# LightSensorCircuitNoAmp_BTSeriesHookup.net
KiCad netlist of a schematic drawn in EAGLE
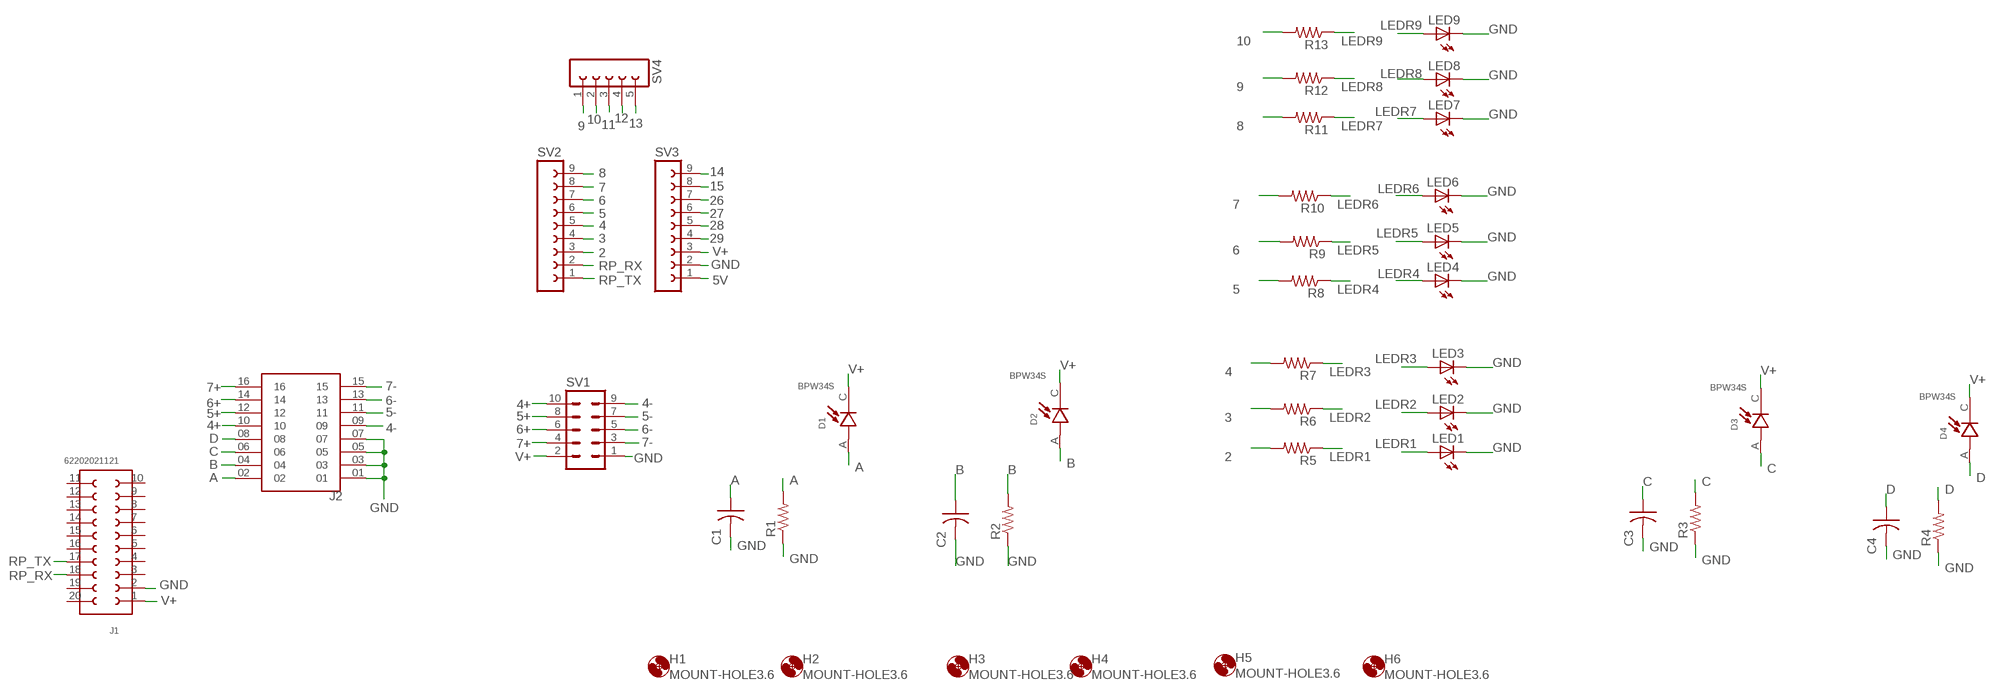
[diagram p0: schematic, sheet 1]

(export (version "E")
  (design (tool "Eeschema 10.0.6"))
  (components
    (comp (ref "C1")
      (value "C-US025-025X050")
      (footprint "eagle-import:C025-025X050")
      (libsource (lib "eagle-import") (part "C-US025-025X050"))
    )
    (comp (ref "C2")
      (value "C-US025-025X050")
      (footprint "eagle-import:C025-025X050")
      (libsource (lib "eagle-import") (part "C-US025-025X050"))
    )
    (comp (ref "C3")
      (value "C-US025-025X050")
      (footprint "eagle-import:C025-025X050")
      (libsource (lib "eagle-import") (part "C-US025-025X050"))
    )
    (comp (ref "C4")
      (value "C-US025-025X050")
      (footprint "eagle-import:C025-025X050")
      (libsource (lib "eagle-import") (part "C-US025-025X050"))
    )
    (comp (ref "D1")
      (value "BPW34S")
      (footprint "eagle-import:DIO_BPW34S")
      (fields (field (name "MF") "Vishay Semiconductor Opto Division"))
      (libsource (lib "eagle-import") (part "BPW34S"))
    )
    (comp (ref "D2")
      (value "BPW34S")
      (footprint "eagle-import:DIO_BPW34S")
      (fields (field (name "MF") "Vishay Semiconductor Opto Division"))
      (libsource (lib "eagle-import") (part "BPW34S"))
    )
    (comp (ref "D3")
      (value "BPW34S")
      (footprint "eagle-import:DIO_BPW34S")
      (fields (field (name "MF") "Vishay Semiconductor Opto Division"))
      (libsource (lib "eagle-import") (part "BPW34S"))
    )
    (comp (ref "D4")
      (value "BPW34S")
      (footprint "eagle-import:DIO_BPW34S")
      (fields (field (name "MF") "Vishay Semiconductor Opto Division"))
      (libsource (lib "eagle-import") (part "BPW34S"))
    )
    (comp (ref "H1")
      (value "MOUNT-HOLE3.6")
      (footprint "eagle-import:3,6")
      (libsource (lib "eagle-import") (part "MOUNT-HOLE3.6"))
    )
    (comp (ref "H2")
      (value "MOUNT-HOLE3.6")
      (footprint "eagle-import:3,6")
      (libsource (lib "eagle-import") (part "MOUNT-HOLE3.6"))
    )
    (comp (ref "H3")
      (value "MOUNT-HOLE3.6")
      (footprint "eagle-import:3,6")
      (libsource (lib "eagle-import") (part "MOUNT-HOLE3.6"))
    )
    (comp (ref "H4")
      (value "MOUNT-HOLE3.6")
      (footprint "eagle-import:3,6")
      (libsource (lib "eagle-import") (part "MOUNT-HOLE3.6"))
    )
    (comp (ref "H5")
      (value "MOUNT-HOLE3.6")
      (footprint "eagle-import:3,6")
      (libsource (lib "eagle-import") (part "MOUNT-HOLE3.6"))
    )
    (comp (ref "H6")
      (value "MOUNT-HOLE3.6")
      (footprint "eagle-import:3,6")
      (libsource (lib "eagle-import") (part "MOUNT-HOLE3.6"))
    )
    (comp (ref "J1")
      (value "62202021121")
      (footprint "eagle-import:62202021121")
      (fields (field (name "MF") "Würth Elektronik"))
      (libsource (lib "eagle-import") (part "62202021121"))
    )
    (comp (ref "J2")
      (value "FTSH-108-02-LM-D-ES")
      (footprint "eagle-import:SAMTEC_FTSH-108-02-LM-D-ES")
      (fields (field (name "MF") "Samtec"))
      (libsource (lib "eagle-import") (part "FTSH-108-02-LM-D-ES"))
    )
    (comp (ref "LED1")
      (value "LEDCHIPLED_1206")
      (footprint "eagle-import:CHIPLED_1206")
      (libsource (lib "eagle-import") (part "LEDCHIPLED_1206"))
    )
    (comp (ref "LED2")
      (value "LEDCHIPLED_1206")
      (footprint "eagle-import:CHIPLED_1206")
      (libsource (lib "eagle-import") (part "LEDCHIPLED_1206"))
    )
    (comp (ref "LED3")
      (value "LEDCHIPLED_1206")
      (footprint "eagle-import:CHIPLED_1206")
      (libsource (lib "eagle-import") (part "LEDCHIPLED_1206"))
    )
    (comp (ref "LED4")
      (value "LEDCHIPLED_1206")
      (footprint "eagle-import:CHIPLED_1206")
      (libsource (lib "eagle-import") (part "LEDCHIPLED_1206"))
    )
    (comp (ref "LED5")
      (value "LEDCHIPLED_1206")
      (footprint "eagle-import:CHIPLED_1206")
      (libsource (lib "eagle-import") (part "LEDCHIPLED_1206"))
    )
    (comp (ref "LED6")
      (value "LEDCHIPLED_1206")
      (footprint "eagle-import:CHIPLED_1206")
      (libsource (lib "eagle-import") (part "LEDCHIPLED_1206"))
    )
    (comp (ref "LED7")
      (value "LEDCHIPLED_1206")
      (footprint "eagle-import:CHIPLED_1206")
      (libsource (lib "eagle-import") (part "LEDCHIPLED_1206"))
    )
    (comp (ref "LED8")
      (value "LEDCHIPLED_1206")
      (footprint "eagle-import:CHIPLED_1206")
      (libsource (lib "eagle-import") (part "LEDCHIPLED_1206"))
    )
    (comp (ref "LED9")
      (value "LEDCHIPLED_1206")
      (footprint "eagle-import:CHIPLED_1206")
      (libsource (lib "eagle-import") (part "LEDCHIPLED_1206"))
    )
    (comp (ref "R1")
      (value "R-US_0204/5")
      (footprint "eagle-import:0204_5")
      (libsource (lib "eagle-import") (part "R-US_0204/5"))
    )
    (comp (ref "R2")
      (value "R-US_0204/5")
      (footprint "eagle-import:0204_5")
      (libsource (lib "eagle-import") (part "R-US_0204/5"))
    )
    (comp (ref "R3")
      (value "R-US_0204/5")
      (footprint "eagle-import:0204_5")
      (libsource (lib "eagle-import") (part "R-US_0204/5"))
    )
    (comp (ref "R4")
      (value "R-US_0204/5")
      (footprint "eagle-import:0204_5")
      (libsource (lib "eagle-import") (part "R-US_0204/5"))
    )
    (comp (ref "R5")
      (value "R-US_0204/5")
      (footprint "eagle-import:0204_5")
      (libsource (lib "eagle-import") (part "R-US_0204/5"))
    )
    (comp (ref "R6")
      (value "R-US_0204/5")
      (footprint "eagle-import:0204_5")
      (libsource (lib "eagle-import") (part "R-US_0204/5"))
    )
    (comp (ref "R7")
      (value "R-US_0204/5")
      (footprint "eagle-import:0204_5")
      (libsource (lib "eagle-import") (part "R-US_0204/5"))
    )
    (comp (ref "R8")
      (value "R-US_0204/5")
      (footprint "eagle-import:0204_5")
      (libsource (lib "eagle-import") (part "R-US_0204/5"))
    )
    (comp (ref "R9")
      (value "R-US_0204/5")
      (footprint "eagle-import:0204_5")
      (libsource (lib "eagle-import") (part "R-US_0204/5"))
    )
    (comp (ref "R10")
      (value "R-US_0204/5")
      (footprint "eagle-import:0204_5")
      (libsource (lib "eagle-import") (part "R-US_0204/5"))
    )
    (comp (ref "R11")
      (value "R-US_0204/5")
      (footprint "eagle-import:0204_5")
      (libsource (lib "eagle-import") (part "R-US_0204/5"))
    )
    (comp (ref "R12")
      (value "R-US_0204/5")
      (footprint "eagle-import:0204_5")
      (libsource (lib "eagle-import") (part "R-US_0204/5"))
    )
    (comp (ref "R13")
      (value "R-US_0204/5")
      (footprint "eagle-import:0204_5")
      (libsource (lib "eagle-import") (part "R-US_0204/5"))
    )
    (comp (ref "SV1")
      (value "MA05-2")
      (footprint "eagle-import:MA05-2")
      (libsource (lib "eagle-import") (part "MA05-2"))
    )
    (comp (ref "SV2")
      (value "FE09-1")
      (footprint "eagle-import:FE09")
      (libsource (lib "eagle-import") (part "FE09-1"))
    )
    (comp (ref "SV3")
      (value "FE09-1")
      (footprint "eagle-import:FE09")
      (libsource (lib "eagle-import") (part "FE09-1"))
    )
    (comp (ref "SV4")
      (value "FE05-1")
      (footprint "eagle-import:FE05-1")
      (libsource (lib "eagle-import") (part "FE05-1"))
    )
  )
  (nets
    (net (code "1") (name "/2") (class "Default")
      (node (ref "R5") (pin "2") (pinfunction "2_2") (pintype "passive"))
      (node (ref "SV2") (pin "3") (pinfunction "3_3") (pintype "passive"))
    )
    (net (code "2") (name "/3") (class "Default")
      (node (ref "R6") (pin "2") (pinfunction "2_2") (pintype "passive"))
      (node (ref "SV2") (pin "4") (pinfunction "4_4") (pintype "passive"))
    )
    (net (code "3") (name "/4") (class "Default")
      (node (ref "R7") (pin "2") (pinfunction "2_2") (pintype "passive"))
      (node (ref "SV2") (pin "5") (pinfunction "5_5") (pintype "passive"))
    )
    (net (code "4") (name "/4+") (class "Default")
      (node (ref "J2") (pin "10") (pinfunction "10_10") (pintype "passive"))
      (node (ref "SV1") (pin "10") (pinfunction "10_10") (pintype "passive"))
    )
    (net (code "5") (name "/4-") (class "Default")
      (node (ref "J2") (pin "09") (pinfunction "09_09") (pintype "passive"))
      (node (ref "SV1") (pin "9") (pinfunction "9_9") (pintype "passive"))
    )
    (net (code "6") (name "/5") (class "Default")
      (node (ref "R8") (pin "2") (pinfunction "2_2") (pintype "passive"))
      (node (ref "SV2") (pin "6") (pinfunction "6_6") (pintype "passive"))
    )
    (net (code "7") (name "/5+") (class "Default")
      (node (ref "J2") (pin "12") (pinfunction "12_12") (pintype "passive"))
      (node (ref "SV1") (pin "8") (pinfunction "8_8") (pintype "passive"))
    )
    (net (code "8") (name "/5-") (class "Default")
      (node (ref "J2") (pin "11") (pinfunction "11_11") (pintype "passive"))
      (node (ref "SV1") (pin "7") (pinfunction "7_7") (pintype "passive"))
    )
    (net (code "9") (name "/5V") (class "Default")
      (node (ref "SV3") (pin "1") (pinfunction "1_1") (pintype "passive"))
    )
    (net (code "10") (name "/6") (class "Default")
      (node (ref "R9") (pin "2") (pinfunction "2_2") (pintype "passive"))
      (node (ref "SV2") (pin "7") (pinfunction "7_7") (pintype "passive"))
    )
    (net (code "11") (name "/6+") (class "Default")
      (node (ref "J2") (pin "14") (pinfunction "14_14") (pintype "passive"))
      (node (ref "SV1") (pin "6") (pinfunction "6_6") (pintype "passive"))
    )
    (net (code "12") (name "/6-") (class "Default")
      (node (ref "J2") (pin "13") (pinfunction "13_13") (pintype "passive"))
      (node (ref "SV1") (pin "5") (pinfunction "5_5") (pintype "passive"))
    )
    (net (code "13") (name "/7") (class "Default")
      (node (ref "R10") (pin "2") (pinfunction "2_2") (pintype "passive"))
      (node (ref "SV2") (pin "8") (pinfunction "8_8") (pintype "passive"))
    )
    (net (code "14") (name "/7+") (class "Default")
      (node (ref "J2") (pin "16") (pinfunction "16_16") (pintype "passive"))
      (node (ref "SV1") (pin "4") (pinfunction "4_4") (pintype "passive"))
    )
    (net (code "15") (name "/7-") (class "Default")
      (node (ref "J2") (pin "15") (pinfunction "15_15") (pintype "passive"))
      (node (ref "SV1") (pin "3") (pinfunction "3_3") (pintype "passive"))
    )
    (net (code "16") (name "/8") (class "Default")
      (node (ref "R11") (pin "2") (pinfunction "2_2") (pintype "passive"))
      (node (ref "SV2") (pin "9") (pinfunction "9_9") (pintype "passive"))
    )
    (net (code "17") (name "/9") (class "Default")
      (node (ref "R12") (pin "2") (pinfunction "2_2") (pintype "passive"))
      (node (ref "SV4") (pin "1") (pinfunction "1_1") (pintype "passive"))
    )
    (net (code "18") (name "/10") (class "Default")
      (node (ref "R13") (pin "2") (pinfunction "2_2") (pintype "passive"))
      (node (ref "SV4") (pin "2") (pinfunction "2_2") (pintype "passive"))
    )
    (net (code "19") (name "/11") (class "Default")
      (node (ref "SV4") (pin "3") (pinfunction "3_3") (pintype "passive"))
    )
    (net (code "20") (name "/12") (class "Default")
      (node (ref "SV4") (pin "4") (pinfunction "4_4") (pintype "passive"))
    )
    (net (code "21") (name "/13") (class "Default")
      (node (ref "SV4") (pin "5") (pinfunction "5_5") (pintype "passive"))
    )
    (net (code "22") (name "/14") (class "Default")
      (node (ref "SV3") (pin "9") (pinfunction "9_9") (pintype "passive"))
    )
    (net (code "23") (name "/15") (class "Default")
      (node (ref "SV3") (pin "8") (pinfunction "8_8") (pintype "passive"))
    )
    (net (code "24") (name "/26") (class "Default")
      (node (ref "SV3") (pin "7") (pinfunction "7_7") (pintype "passive"))
    )
    (net (code "25") (name "/27") (class "Default")
      (node (ref "SV3") (pin "6") (pinfunction "6_6") (pintype "passive"))
    )
    (net (code "26") (name "/28") (class "Default")
      (node (ref "SV3") (pin "5") (pinfunction "5_5") (pintype "passive"))
    )
    (net (code "27") (name "/29") (class "Default")
      (node (ref "SV3") (pin "4") (pinfunction "4_4") (pintype "passive"))
    )
    (net (code "28") (name "/A") (class "Default")
      (node (ref "C1") (pin "1") (pinfunction "1_1") (pintype "passive"))
      (node (ref "D1") (pin "A") (pinfunction "A_A") (pintype "passive"))
      (node (ref "J2") (pin "02") (pinfunction "02_02") (pintype "passive"))
      (node (ref "R1") (pin "2") (pinfunction "2_2") (pintype "passive"))
    )
    (net (code "29") (name "/B") (class "Default")
      (node (ref "C2") (pin "1") (pinfunction "1_1") (pintype "passive"))
      (node (ref "D2") (pin "A") (pinfunction "A_A") (pintype "passive"))
      (node (ref "J2") (pin "04") (pinfunction "04_04") (pintype "passive"))
      (node (ref "R2") (pin "2") (pinfunction "2_2") (pintype "passive"))
    )
    (net (code "30") (name "/C") (class "Default")
      (node (ref "C3") (pin "1") (pinfunction "1_1") (pintype "passive"))
      (node (ref "D3") (pin "A") (pinfunction "A_A") (pintype "passive"))
      (node (ref "J2") (pin "06") (pinfunction "06_06") (pintype "passive"))
      (node (ref "R3") (pin "2") (pinfunction "2_2") (pintype "passive"))
    )
    (net (code "31") (name "/D") (class "Default")
      (node (ref "C4") (pin "1") (pinfunction "1_1") (pintype "passive"))
      (node (ref "D4") (pin "A") (pinfunction "A_A") (pintype "passive"))
      (node (ref "J2") (pin "08") (pinfunction "08_08") (pintype "passive"))
      (node (ref "R4") (pin "2") (pinfunction "2_2") (pintype "passive"))
    )
    (net (code "32") (name "/GND") (class "Default")
      (node (ref "C1") (pin "2") (pinfunction "2_2") (pintype "passive"))
      (node (ref "C2") (pin "2") (pinfunction "2_2") (pintype "passive"))
      (node (ref "C3") (pin "2") (pinfunction "2_2") (pintype "passive"))
      (node (ref "C4") (pin "2") (pinfunction "2_2") (pintype "passive"))
      (node (ref "J1") (pin "2") (pinfunction "2_2") (pintype "passive"))
      (node (ref "J2") (pin "01") (pinfunction "01_01") (pintype "passive"))
      (node (ref "J2") (pin "03") (pinfunction "03_03") (pintype "passive"))
      (node (ref "J2") (pin "05") (pinfunction "05_05") (pintype "passive"))
      (node (ref "J2") (pin "07") (pinfunction "07_07") (pintype "passive"))
      (node (ref "LED1") (pin "C") (pinfunction "C_C") (pintype "passive"))
      (node (ref "LED2") (pin "C") (pinfunction "C_C") (pintype "passive"))
      (node (ref "LED3") (pin "C") (pinfunction "C_C") (pintype "passive"))
      (node (ref "LED4") (pin "C") (pinfunction "C_C") (pintype "passive"))
      (node (ref "LED5") (pin "C") (pinfunction "C_C") (pintype "passive"))
      (node (ref "LED6") (pin "C") (pinfunction "C_C") (pintype "passive"))
      (node (ref "LED7") (pin "C") (pinfunction "C_C") (pintype "passive"))
      (node (ref "LED8") (pin "C") (pinfunction "C_C") (pintype "passive"))
      (node (ref "LED9") (pin "C") (pinfunction "C_C") (pintype "passive"))
      (node (ref "R1") (pin "1") (pinfunction "1_1") (pintype "passive"))
      (node (ref "R2") (pin "1") (pinfunction "1_1") (pintype "passive"))
      (node (ref "R3") (pin "1") (pinfunction "1_1") (pintype "passive"))
      (node (ref "R4") (pin "1") (pinfunction "1_1") (pintype "passive"))
      (node (ref "SV1") (pin "1") (pinfunction "1_1") (pintype "passive"))
      (node (ref "SV3") (pin "2") (pinfunction "2_2") (pintype "passive"))
    )
    (net (code "33") (name "/LEDR1") (class "Default")
      (node (ref "LED1") (pin "A") (pinfunction "A_A") (pintype "passive"))
      (node (ref "R5") (pin "1") (pinfunction "1_1") (pintype "passive"))
    )
    (net (code "34") (name "/LEDR2") (class "Default")
      (node (ref "LED2") (pin "A") (pinfunction "A_A") (pintype "passive"))
      (node (ref "R6") (pin "1") (pinfunction "1_1") (pintype "passive"))
    )
    (net (code "35") (name "/LEDR3") (class "Default")
      (node (ref "LED3") (pin "A") (pinfunction "A_A") (pintype "passive"))
      (node (ref "R7") (pin "1") (pinfunction "1_1") (pintype "passive"))
    )
    (net (code "36") (name "/LEDR4") (class "Default")
      (node (ref "LED4") (pin "A") (pinfunction "A_A") (pintype "passive"))
      (node (ref "R8") (pin "1") (pinfunction "1_1") (pintype "passive"))
    )
    (net (code "37") (name "/LEDR5") (class "Default")
      (node (ref "LED5") (pin "A") (pinfunction "A_A") (pintype "passive"))
      (node (ref "R9") (pin "1") (pinfunction "1_1") (pintype "passive"))
    )
    (net (code "38") (name "/LEDR6") (class "Default")
      (node (ref "LED6") (pin "A") (pinfunction "A_A") (pintype "passive"))
      (node (ref "R10") (pin "1") (pinfunction "1_1") (pintype "passive"))
    )
    (net (code "39") (name "/LEDR7") (class "Default")
      (node (ref "LED7") (pin "A") (pinfunction "A_A") (pintype "passive"))
      (node (ref "R11") (pin "1") (pinfunction "1_1") (pintype "passive"))
    )
    (net (code "40") (name "/LEDR8") (class "Default")
      (node (ref "LED8") (pin "A") (pinfunction "A_A") (pintype "passive"))
      (node (ref "R12") (pin "1") (pinfunction "1_1") (pintype "passive"))
    )
    (net (code "41") (name "/LEDR9") (class "Default")
      (node (ref "LED9") (pin "A") (pinfunction "A_A") (pintype "passive"))
      (node (ref "R13") (pin "1") (pinfunction "1_1") (pintype "passive"))
    )
    (net (code "42") (name "/RP_RX") (class "Default")
      (node (ref "J1") (pin "18") (pinfunction "18_18") (pintype "passive"))
      (node (ref "SV2") (pin "2") (pinfunction "2_2") (pintype "passive"))
    )
    (net (code "43") (name "/RP_TX") (class "Default")
      (node (ref "J1") (pin "17") (pinfunction "17_17") (pintype "passive"))
      (node (ref "SV2") (pin "1") (pinfunction "1_1") (pintype "passive"))
    )
    (net (code "44") (name "/V+") (class "Default")
      (node (ref "D1") (pin "C") (pinfunction "C_C") (pintype "passive"))
      (node (ref "D2") (pin "C") (pinfunction "C_C") (pintype "passive"))
      (node (ref "D3") (pin "C") (pinfunction "C_C") (pintype "passive"))
      (node (ref "D4") (pin "C") (pinfunction "C_C") (pintype "passive"))
      (node (ref "J1") (pin "1") (pinfunction "1_1") (pintype "passive"))
      (node (ref "SV1") (pin "2") (pinfunction "2_2") (pintype "passive"))
      (node (ref "SV3") (pin "3") (pinfunction "3_3") (pintype "passive"))
    )
    (net (code "45") (name "unconnected-(J1-Pad3)") (class "Default")
      (node (ref "J1") (pin "3") (pinfunction "3_3") (pintype "passive"))
    )
    (net (code "46") (name "unconnected-(J1-Pad4)") (class "Default")
      (node (ref "J1") (pin "4") (pinfunction "4_4") (pintype "passive"))
    )
    (net (code "47") (name "unconnected-(J1-Pad5)") (class "Default")
      (node (ref "J1") (pin "5") (pinfunction "5_5") (pintype "passive"))
    )
    (net (code "48") (name "unconnected-(J1-Pad6)") (class "Default")
      (node (ref "J1") (pin "6") (pinfunction "6_6") (pintype "passive"))
    )
    (net (code "49") (name "unconnected-(J1-Pad7)") (class "Default")
      (node (ref "J1") (pin "7") (pinfunction "7_7") (pintype "passive"))
    )
    (net (code "50") (name "unconnected-(J1-Pad8)") (class "Default")
      (node (ref "J1") (pin "8") (pinfunction "8_8") (pintype "passive"))
    )
    (net (code "51") (name "unconnected-(J1-Pad9)") (class "Default")
      (node (ref "J1") (pin "9") (pinfunction "9_9") (pintype "passive"))
    )
    (net (code "52") (name "unconnected-(J1-Pad10)") (class "Default")
      (node (ref "J1") (pin "10") (pinfunction "10_10") (pintype "passive"))
    )
    (net (code "53") (name "unconnected-(J1-Pad11)") (class "Default")
      (node (ref "J1") (pin "11") (pinfunction "11_11") (pintype "passive"))
    )
    (net (code "54") (name "unconnected-(J1-Pad12)") (class "Default")
      (node (ref "J1") (pin "12") (pinfunction "12_12") (pintype "passive"))
    )
    (net (code "55") (name "unconnected-(J1-Pad13)") (class "Default")
      (node (ref "J1") (pin "13") (pinfunction "13_13") (pintype "passive"))
    )
    (net (code "56") (name "unconnected-(J1-Pad14)") (class "Default")
      (node (ref "J1") (pin "14") (pinfunction "14_14") (pintype "passive"))
    )
    (net (code "57") (name "unconnected-(J1-Pad15)") (class "Default")
      (node (ref "J1") (pin "15") (pinfunction "15_15") (pintype "passive"))
    )
    (net (code "58") (name "unconnected-(J1-Pad16)") (class "Default")
      (node (ref "J1") (pin "16") (pinfunction "16_16") (pintype "passive"))
    )
    (net (code "59") (name "unconnected-(J1-Pad19)") (class "Default")
      (node (ref "J1") (pin "19") (pinfunction "19_19") (pintype "passive"))
    )
    (net (code "60") (name "unconnected-(J1-Pad20)") (class "Default")
      (node (ref "J1") (pin "20") (pinfunction "20_20") (pintype "passive"))
    )
  )
)
